# Connections1.net
KiCad netlist of a schematic drawn in Altium Designer
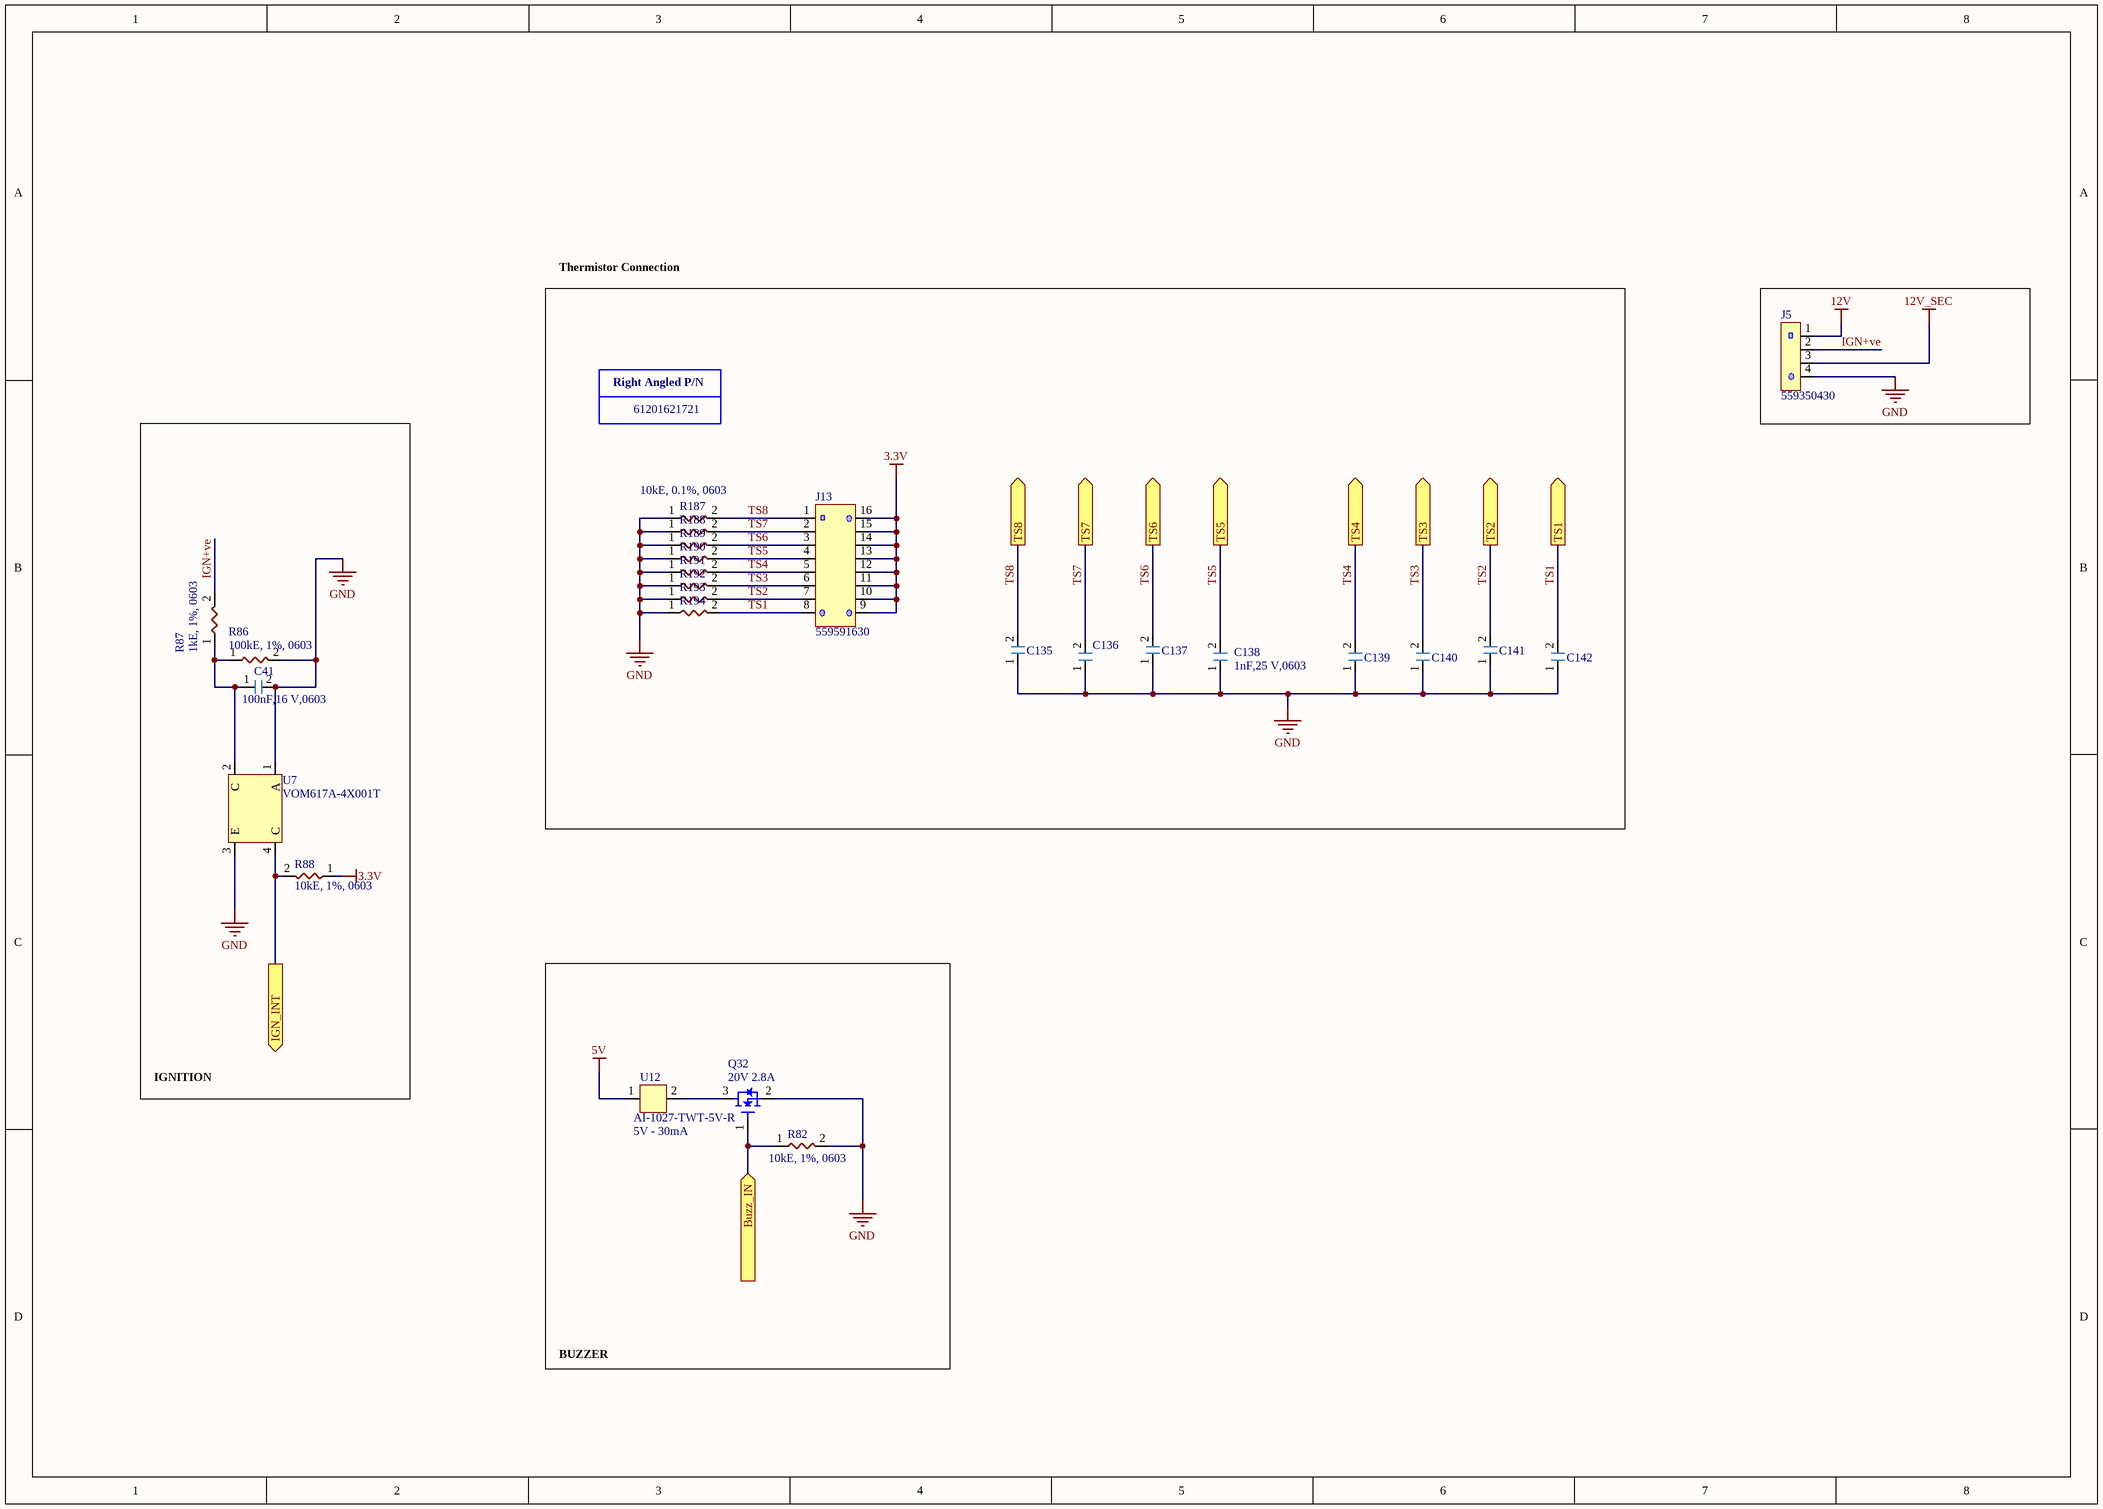
[diagram p0: Connections1.SchDoc]

(export (version "E")
  (design (tool "Eeschema 10.0.6"))
  (components
    (comp (ref "C41")
      (value "CC0603KRX7R7BB104")
      (footprint "BMS_V2.1_Adv:CAPC1608X05N 0603")
      (description "Multilayer Ceramic Capacitor, 100 nF, 16V, ±10%,  X7R 0603 [1608 Metric]")
      (fields
        (field (name "MANUFACTURER") "Yageo")
        (field (name "TOLERANCE") "10%")
        (field (name "VALUE DISPLAY") "100nF,16 V,0603")
      )
      (libsource (lib "BMS_V2.1_Adv") (part "Cap_CC0603KRX7R7BB104"))
    )
    (comp (ref "C135")
      (value "C0603C102J3GACAUTO")
      (footprint "CAPC1608X05N 0603")
      (description "Multilayer Ceramic Capacitor, 1000 pF, 25V, ±5%,  C0G 0603 [1608 Metric]")
      (fields (field (name "MANUFACTURER") "KEMET") (field (name "VOLTAGE") "25V"))
      (libsource (lib "BMS_V2.1_Adv") (part "Cap_C0603C102J3GACAUTO"))
    )
    (comp (ref "C136")
      (value "C0603C102J3GACAUTO")
      (footprint "CAPC1608X05N 0603")
      (description "Multilayer Ceramic Capacitor, 1000 pF, 25V, ±5%,  C0G 0603 [1608 Metric]")
      (fields (field (name "MANUFACTURER") "KEMET") (field (name "VOLTAGE") "25V"))
      (libsource (lib "BMS_V2.1_Adv") (part "Cap_C0603C102J3GACAUTO"))
    )
    (comp (ref "C137")
      (value "C0603C102J3GACAUTO")
      (footprint "CAPC1608X05N 0603")
      (description "Multilayer Ceramic Capacitor, 1000 pF, 25V, ±5%,  C0G 0603 [1608 Metric]")
      (fields (field (name "MANUFACTURER") "KEMET") (field (name "VOLTAGE") "25V"))
      (libsource (lib "BMS_V2.1_Adv") (part "Cap_C0603C102J3GACAUTO"))
    )
    (comp (ref "C138")
      (value "C0603C102J3GACAUTO")
      (footprint "CAPC1608X05N 0603")
      (description "Multilayer Ceramic Capacitor, 1000 pF, 25V, ±5%,  C0G 0603 [1608 Metric]")
      (fields
        (field (name "MANUFACTURER") "KEMET")
        (field (name "VOLTAGE") "25V")
        (field (name "VALUE DISPLAY") "1nF,25 V,0603")
      )
      (libsource (lib "BMS_V2.1_Adv") (part "Cap_C0603C102J3GACAUTO"))
    )
    (comp (ref "C139")
      (value "C0603C102J3GACAUTO")
      (footprint "CAPC1608X05N 0603")
      (description "Multilayer Ceramic Capacitor, 1000 pF, 25V, ±5%,  C0G 0603 [1608 Metric]")
      (fields (field (name "MANUFACTURER") "KEMET") (field (name "VOLTAGE") "25V"))
      (libsource (lib "BMS_V2.1_Adv") (part "Cap_C0603C102J3GACAUTO"))
    )
    (comp (ref "C140")
      (value "C0603C102J3GACAUTO")
      (footprint "CAPC1608X05N 0603")
      (description "Multilayer Ceramic Capacitor, 1000 pF, 25V, ±5%,  C0G 0603 [1608 Metric]")
      (fields (field (name "MANUFACTURER") "KEMET") (field (name "VOLTAGE") "25V"))
      (libsource (lib "BMS_V2.1_Adv") (part "Cap_C0603C102J3GACAUTO"))
    )
    (comp (ref "C141")
      (value "C0603C102J3GACAUTO")
      (footprint "CAPC1608X05N 0603")
      (description "Multilayer Ceramic Capacitor, 1000 pF, 25V, ±5%,  C0G 0603 [1608 Metric]")
      (fields (field (name "MANUFACTURER") "KEMET") (field (name "VOLTAGE") "25V"))
      (libsource (lib "BMS_V2.1_Adv") (part "Cap_C0603C102J3GACAUTO"))
    )
    (comp (ref "C142")
      (value "C0603C102J3GACAUTO")
      (footprint "CAPC1608X05N 0603")
      (description "Multilayer Ceramic Capacitor, 1000 pF, 25V, ±5%,  C0G 0603 [1608 Metric]")
      (fields (field (name "MANUFACTURER") "KEMET") (field (name "VOLTAGE") "25V"))
      (libsource (lib "BMS_V2.1_Adv") (part "Cap_C0603C102J3GACAUTO"))
    )
    (comp (ref "J5")
      (value "559350430")
      (footprint "BMS_V2.1_Adv:Con_559350430")
      (description "2.00mm Pitch MicroClasp Wire-to-Board Header, Dual Row, Right Angle, 4 Circuits")
      (fields (field (name "CRIMP PART NUMBER") "561349000") (field (name "MANUFACTURER") "Molex"))
      (libsource (lib "BMS_V2.1_Adv") (part "Con_559350430"))
    )
    (comp (ref "J13")
      (value "559591630")
      (footprint "Etop PCB:Con_0559591630")
      (description "2.00mm Pitch MicroClasp Wire-to-Board Header, Dual Row, Right Angle, 16 Circuits")
      (fields (field (name "CRIMP PART NUMBER") "561349000") (field (name "MANUFACTURER") "Molex"))
      (libsource (lib "BMS_V2.1_Adv") (part "Con_559591630"))
    )
    (comp (ref "Q32")
      (value "DMG2302UK-7")
      (footprint "BMS_V2.1_Adv:SOT95P255X140-3N")
      (description "N-Channel 20 V 2.8A (Ta) 660mW (Ta) Surface Mount SOT-23-3")
      (fields
        (field (name "MANUFACTURER") "Diodes Inc.")
        (field (name "POWER") "660mW")
        (field (name "VALUE DISPLAY") "20V 2.8A")
      )
      (libsource (lib "BMS_V2.1_Adv") (part "FET_DMG2302UK-7"))
    )
    (comp (ref "R82")
      (value "CRCW060310K0FKEA")
      (footprint "BMS_V2.1_Adv:RESC1608X05N 0603")
      (description "SMD Chip Resistor, 10 kOhm,±1%, 100 mW, 0603 [1608 Metric], Thick Film, General Purpose")
      (fields
        (field (name "MANUFACTURER") "Vishay Dale")
        (field (name "POWER") "1/10W")
        (field (name "VALUE DISPLAY") "10kE, 1%, 0603")
      )
      (libsource (lib "BMS_V2.1_Adv") (part "Res_CRCW060310K0FKEA"))
    )
    (comp (ref "R86")
      (value "CRCW0805100KFKEA")
      (footprint "BMS_V2.1_Adv:RESC1608X05N 0603")
      (description "SMD Chip Resistor, 100k Ohm, ± 1%, 100 mW, 0603 [1608 Metric], Thick Film, General Purpose")
      (fields
        (field (name "MANUFACTURER") "Vishay Dale")
        (field (name "MANUFACTURER PART NUMBER") "CRCW0603100KFKEA")
        (field (name "VALUE DISPLAY") "100kE, 1%, 0603")
      )
      (libsource (lib "BMS_V2.1_Adv") (part "Res_CRCW0603100KFKEA"))
    )
    (comp (ref "R87")
      (value "AC0603FR-7W1KL")
      (footprint "BMS_V2.1_Adv:RESC1608X05N 0603")
      (fields
        (field (name "MANUFACTURER") "Yageo")
        (field (name "POWER") "1/5 W")
        (field (name "TOLERANCE") "1%")
        (field (name "VALUE DISPLAY") "1kE, 1%, 0603")
      )
      (libsource (lib "BMS_V2.1_Adv") (part "Res_AC0603FR-7W1KL"))
    )
    (comp (ref "R88")
      (value "CRCW060310K0FKEA")
      (footprint "BMS_V2.1_Adv:RESC1608X05N 0603")
      (description "SMD Chip Resistor, 10 kOhm,±1%, 100 mW, 0603 [1608 Metric], Thick Film, General Purpose")
      (fields
        (field (name "MANUFACTURER") "Vishay Dale")
        (field (name "POWER") "1/10W")
        (field (name "VALUE DISPLAY") "10kE, 1%, 0603")
      )
      (libsource (lib "BMS_V2.1_Adv") (part "Res_CRCW060310K0FKEA"))
    )
    (comp (ref "R187")
      (value "RNCF0603BTE10K0")
      (footprint "RESC1608X05N 0603")
      (fields
        (field (name "MANUFACTURER") "Stackpole Electronics")
        (field (name "TOLERANCE") "0.1%")
        (field (name "POWER") "1/6W")
        (field (name "VALUE DISPLAY") "10kE, 0.1%, 0603")
      )
      (libsource (lib "BMS_V2.1_Adv") (part "Res_RNCF0603BTE10K0"))
    )
    (comp (ref "R188")
      (value "RNCF0603BTE10K0")
      (footprint "RESC1608X05N 0603")
      (fields
        (field (name "MANUFACTURER") "Stackpole Electronics")
        (field (name "TOLERANCE") "0.1%")
        (field (name "POWER") "1/6W")
      )
      (libsource (lib "BMS_V2.1_Adv") (part "Res_RNCF0603BTE10K0"))
    )
    (comp (ref "R189")
      (value "RNCF0603BTE10K0")
      (footprint "RESC1608X05N 0603")
      (fields
        (field (name "MANUFACTURER") "Stackpole Electronics")
        (field (name "TOLERANCE") "0.1%")
        (field (name "POWER") "1/6W")
      )
      (libsource (lib "BMS_V2.1_Adv") (part "Res_RNCF0603BTE10K0"))
    )
    (comp (ref "R190")
      (value "RNCF0603BTE10K0")
      (footprint "RESC1608X05N 0603")
      (fields
        (field (name "MANUFACTURER") "Stackpole Electronics")
        (field (name "TOLERANCE") "0.1%")
        (field (name "POWER") "1/6W")
      )
      (libsource (lib "BMS_V2.1_Adv") (part "Res_RNCF0603BTE10K0"))
    )
    (comp (ref "R191")
      (value "RNCF0603BTE10K0")
      (footprint "RESC1608X05N 0603")
      (fields
        (field (name "MANUFACTURER") "Stackpole Electronics")
        (field (name "TOLERANCE") "0.1%")
        (field (name "POWER") "1/6W")
      )
      (libsource (lib "BMS_V2.1_Adv") (part "Res_RNCF0603BTE10K0"))
    )
    (comp (ref "R192")
      (value "RNCF0603BTE10K0")
      (footprint "RESC1608X05N 0603")
      (fields
        (field (name "MANUFACTURER") "Stackpole Electronics")
        (field (name "TOLERANCE") "0.1%")
        (field (name "POWER") "1/6W")
      )
      (libsource (lib "BMS_V2.1_Adv") (part "Res_RNCF0603BTE10K0"))
    )
    (comp (ref "R193")
      (value "RNCF0603BTE10K0")
      (footprint "RESC1608X05N 0603")
      (fields
        (field (name "MANUFACTURER") "Stackpole Electronics")
        (field (name "TOLERANCE") "0.1%")
        (field (name "POWER") "1/6W")
      )
      (libsource (lib "BMS_V2.1_Adv") (part "Res_RNCF0603BTE10K0"))
    )
    (comp (ref "R194")
      (value "RNCF0603BTE10K0")
      (footprint "RESC1608X05N 0603")
      (fields
        (field (name "MANUFACTURER") "Stackpole Electronics")
        (field (name "TOLERANCE") "0.1%")
        (field (name "POWER") "1/6W")
      )
      (libsource (lib "BMS_V2.1_Adv") (part "Res_RNCF0603BTE10K0"))
    )
    (comp (ref "U7")
      (value "VOM617A-4X001T")
      (footprint "BMS_V2.1_Adv:SOIC127P700X220-4N TLP293")
      (description "Optoisolator Transistor Output 3750Vrms 1 Channel 4-SOP")
      (fields (field (name "MANUFACTURER") "Vishay Dale") (field (name "VOLTAGE") "3750 VRMS"))
      (libsource (lib "BMS_V2.1_Adv") (part "IC_VOM617A-4X001T"))
    )
    (comp (ref "U12")
      (value "AI-1027-TWT-5V-R")
      (footprint "BMS_V2.1_Adv:Buzzer")
      (fields
        (field (name "MANUFACTURER") "PUIaudio")
        (field (name "VALUE DISPLAY") "5V - 30mA")
        (field (name "VOLTAGE") "5V")
      )
      (libsource (lib "BMS_V2.1_Adv") (part "IC_AI-1027-TWT-5V-R"))
    )
  )
  (nets
    (net (code "1") (name "/Buzz_IN") (class "Default")
      (node (ref "Q32") (pin "1") (pinfunction "Gate_1") (pintype "passive"))
      (node (ref "R82") (pin "1") (pinfunction "1_1") (pintype "passive"))
    )
    (net (code "2") (name "/IGN+ve") (class "Default")
      (node (ref "J5") (pin "2") (pinfunction "2_2") (pintype "passive"))
      (node (ref "R87") (pin "2") (pinfunction "2_2") (pintype "passive"))
    )
    (net (code "3") (name "/IGN_INT") (class "Default")
      (node (ref "R88") (pin "2") (pinfunction "2_2") (pintype "passive"))
      (node (ref "U7") (pin "4") (pinfunction "C_4") (pintype "passive"))
    )
    (net (code "4") (name "/TS1") (class "Default")
      (node (ref "C142") (pin "2") (pinfunction "2_2") (pintype "passive"))
      (node (ref "J13") (pin "8") (pintype "passive"))
      (node (ref "R194") (pin "2") (pinfunction "2_2") (pintype "passive"))
    )
    (net (code "5") (name "/TS2") (class "Default")
      (node (ref "C141") (pin "2") (pinfunction "2_2") (pintype "passive"))
      (node (ref "J13") (pin "7") (pintype "passive"))
      (node (ref "R193") (pin "2") (pinfunction "2_2") (pintype "passive"))
    )
    (net (code "6") (name "/TS3") (class "Default")
      (node (ref "C140") (pin "2") (pinfunction "2_2") (pintype "passive"))
      (node (ref "J13") (pin "6") (pintype "passive"))
      (node (ref "R192") (pin "2") (pinfunction "2_2") (pintype "passive"))
    )
    (net (code "7") (name "/TS4") (class "Default")
      (node (ref "C139") (pin "2") (pinfunction "2_2") (pintype "passive"))
      (node (ref "J13") (pin "5") (pintype "passive"))
      (node (ref "R191") (pin "2") (pinfunction "2_2") (pintype "passive"))
    )
    (net (code "8") (name "/TS5") (class "Default")
      (node (ref "C138") (pin "2") (pinfunction "2_2") (pintype "passive"))
      (node (ref "J13") (pin "4") (pintype "passive"))
      (node (ref "R190") (pin "2") (pinfunction "2_2") (pintype "passive"))
    )
    (net (code "9") (name "/TS6") (class "Default")
      (node (ref "C137") (pin "2") (pinfunction "2_2") (pintype "passive"))
      (node (ref "J13") (pin "3") (pintype "passive"))
      (node (ref "R189") (pin "2") (pinfunction "2_2") (pintype "passive"))
    )
    (net (code "10") (name "/TS7") (class "Default")
      (node (ref "C136") (pin "2") (pinfunction "2_2") (pintype "passive"))
      (node (ref "J13") (pin "2") (pintype "passive"))
      (node (ref "R188") (pin "2") (pinfunction "2_2") (pintype "passive"))
    )
    (net (code "11") (name "/TS8") (class "Default")
      (node (ref "C135") (pin "2") (pinfunction "2_2") (pintype "passive"))
      (node (ref "J13") (pin "1") (pintype "passive"))
      (node (ref "R187") (pin "2") (pinfunction "2_2") (pintype "passive"))
    )
    (net (code "12") (name "3.3V") (class "Default")
      (node (ref "J13") (pin "10") (pintype "passive"))
      (node (ref "J13") (pin "11") (pintype "passive"))
      (node (ref "J13") (pin "12") (pintype "passive"))
      (node (ref "J13") (pin "13") (pinfunction "13_13") (pintype "passive"))
      (node (ref "J13") (pin "14") (pinfunction "14_14") (pintype "passive"))
      (node (ref "J13") (pin "15") (pinfunction "15_15") (pintype "passive"))
      (node (ref "J13") (pin "16") (pinfunction "16_16") (pintype "passive"))
      (node (ref "J13") (pin "9") (pintype "passive"))
      (node (ref "R88") (pin "1") (pinfunction "1_1") (pintype "passive"))
    )
    (net (code "13") (name "5V") (class "Default")
      (node (ref "U12") (pin "1") (pinfunction "+ve_1") (pintype "passive"))
    )
    (net (code "14") (name "12V") (class "Default")
      (node (ref "J5") (pin "1") (pinfunction "1_1") (pintype "passive"))
    )
    (net (code "15") (name "12V_SEC") (class "Default")
      (node (ref "J5") (pin "3") (pinfunction "3_3") (pintype "passive"))
    )
    (net (code "16") (name "GND") (class "Default")
      (node (ref "C135") (pin "1") (pinfunction "1_1") (pintype "passive"))
      (node (ref "C136") (pin "1") (pinfunction "1_1") (pintype "passive"))
      (node (ref "C137") (pin "1") (pinfunction "1_1") (pintype "passive"))
      (node (ref "C138") (pin "1") (pinfunction "1_1") (pintype "passive"))
      (node (ref "C139") (pin "1") (pinfunction "1_1") (pintype "passive"))
      (node (ref "C140") (pin "1") (pinfunction "1_1") (pintype "passive"))
      (node (ref "C141") (pin "1") (pinfunction "1_1") (pintype "passive"))
      (node (ref "C142") (pin "1") (pinfunction "1_1") (pintype "passive"))
      (node (ref "C41") (pin "2") (pinfunction "2_2") (pintype "passive"))
      (node (ref "J5") (pin "4") (pinfunction "4_4") (pintype "passive"))
      (node (ref "Q32") (pin "2") (pinfunction "Source_2") (pintype "passive"))
      (node (ref "R187") (pin "1") (pinfunction "1_1") (pintype "passive"))
      (node (ref "R188") (pin "1") (pinfunction "1_1") (pintype "passive"))
      (node (ref "R189") (pin "1") (pinfunction "1_1") (pintype "passive"))
      (node (ref "R190") (pin "1") (pinfunction "1_1") (pintype "passive"))
      (node (ref "R191") (pin "1") (pinfunction "1_1") (pintype "passive"))
      (node (ref "R192") (pin "1") (pinfunction "1_1") (pintype "passive"))
      (node (ref "R193") (pin "1") (pinfunction "1_1") (pintype "passive"))
      (node (ref "R194") (pin "1") (pinfunction "1_1") (pintype "passive"))
      (node (ref "R82") (pin "2") (pinfunction "2_2") (pintype "passive"))
      (node (ref "R86") (pin "2") (pinfunction "2_2") (pintype "passive"))
      (node (ref "U7") (pin "1") (pinfunction "A_1") (pintype "passive"))
      (node (ref "U7") (pin "3") (pinfunction "E_3") (pintype "passive"))
    )
    (net (code "17") (name "Net-(C41-Pad1)") (class "Default")
      (node (ref "C41") (pin "1") (pinfunction "1_1") (pintype "passive"))
      (node (ref "R86") (pin "1") (pinfunction "1_1") (pintype "passive"))
      (node (ref "R87") (pin "1") (pinfunction "1_1") (pintype "passive"))
      (node (ref "U7") (pin "2") (pinfunction "C_2") (pintype "passive"))
    )
    (net (code "18") (name "Net-(Q32-Drain)") (class "Default")
      (node (ref "Q32") (pin "3") (pinfunction "Drain_3") (pintype "passive"))
      (node (ref "U12") (pin "2") (pinfunction "-ve_2") (pintype "passive"))
    )
  )
)
